# MCU.net
KiCad netlist of a schematic drawn in Altium Designer
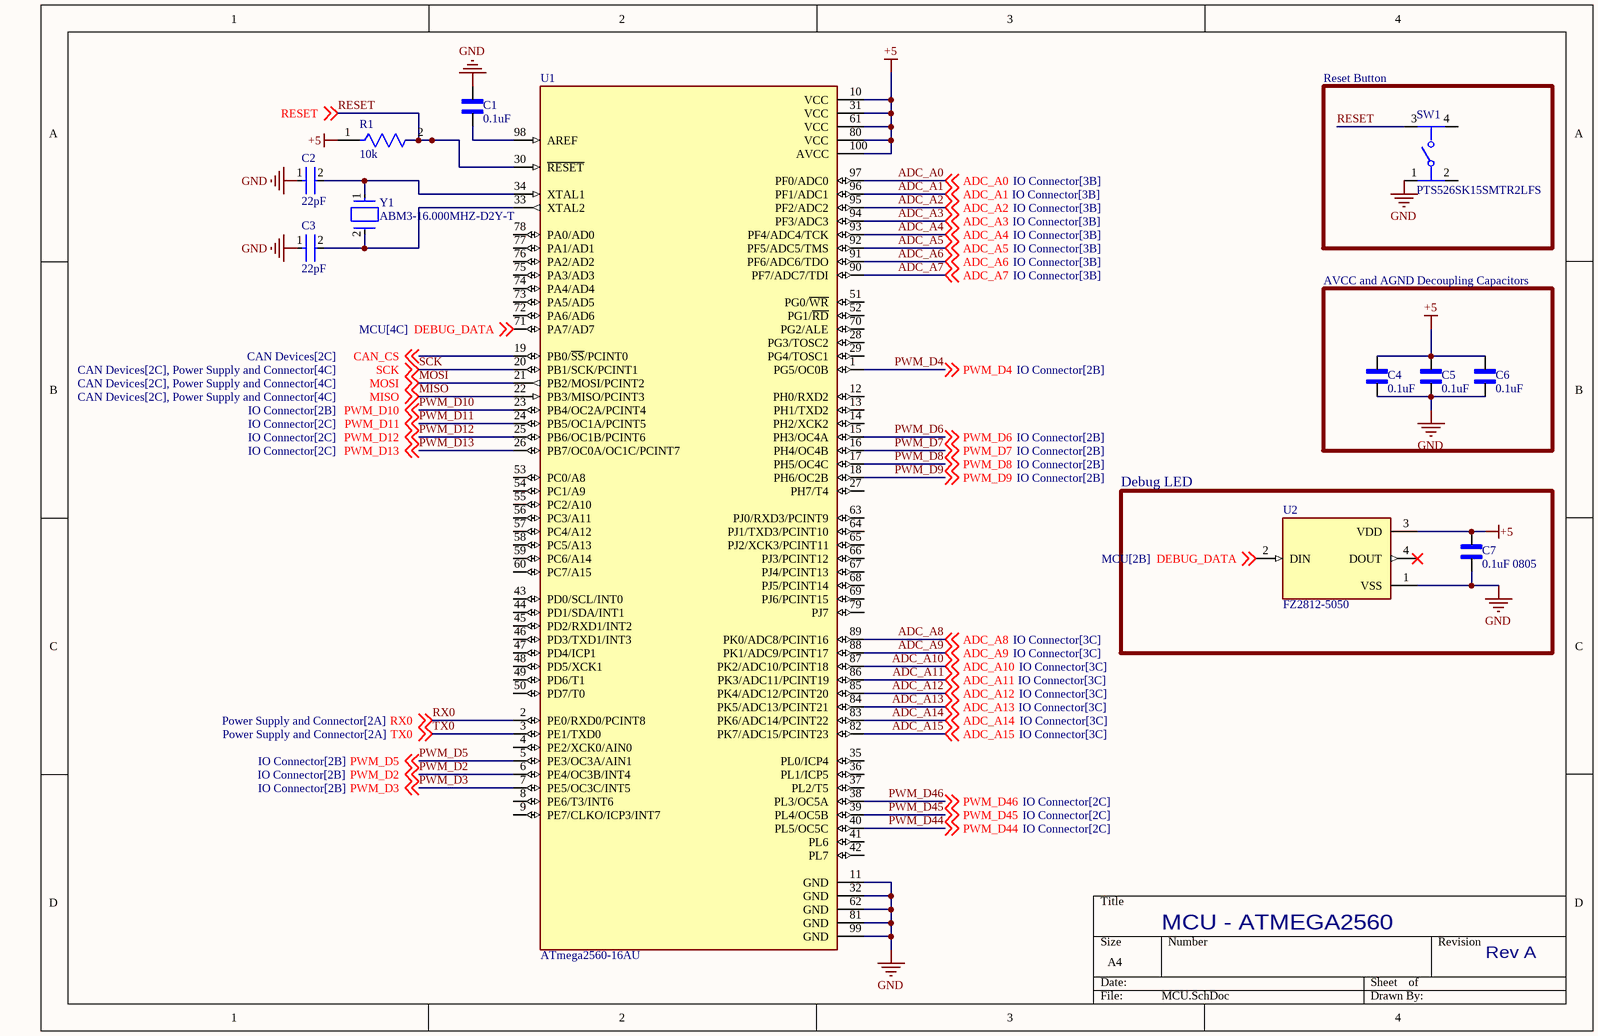
[diagram p0: MCU.SchDoc]

(export (version "E")
  (design (tool "Eeschema 10.0.6"))
  (components
    (comp (ref "C1")
      (value "0.1uF")
      (footprint "GCM21BR71H104KA37L:CAPC2012X135N")
      (description "CAP, MLCC, X7R, 0.1UF, 50V, 0805")
      (fields (field (name "MF") "{'manufacturer': u'Murata'}") (field (name "MP") "GCM21BR71H104KA37L"))
      (libsource (lib "*") (part "GCM21BR71H104KA37L"))
    )
    (comp (ref "C2")
      (value "22pF")
      (footprint "FP-C0805C-DN-MFG")
      (description "CAP CER 22PF 100V 5% NP0 0805")
      (fields
        (field (name "OCTOPART") "https://octopart.com/c0805c220j1gactu-kemet-3791395")
        (field (name "TOLERANCE") "0.05")
      )
      (libsource (lib "Altium Content Vault") (part "b4654b650e69147ec39a6b967a45e02"))
    )
    (comp (ref "C3")
      (value "22pF")
      (footprint "FP-C0805C-DN-MFG")
      (description "CAP CER 22PF 100V 5% NP0 0805")
      (fields
        (field (name "OCTOPART") "https://octopart.com/c0805c220j1gactu-kemet-3791395")
        (field (name "TOLERANCE") "0.05")
      )
      (libsource (lib "Altium Content Vault") (part "b4654b650e69147ec39a6b967a45e02"))
    )
    (comp (ref "C4")
      (value "0.1uF")
      (footprint "GCM21BR71H104KA37L:CAPC2012X135N")
      (description "CAP, MLCC, X7R, 0.1UF, 50V, 0805")
      (fields (field (name "MF") "{'manufacturer': u'Murata'}") (field (name "MP") "GCM21BR71H104KA37L"))
      (libsource (lib "*") (part "GCM21BR71H104KA37L"))
    )
    (comp (ref "C5")
      (value "0.1uF")
      (footprint "GCM21BR71H104KA37L:CAPC2012X135N")
      (description "CAP, MLCC, X7R, 0.1UF, 50V, 0805")
      (fields (field (name "MF") "{'manufacturer': u'Murata'}") (field (name "MP") "GCM21BR71H104KA37L"))
      (libsource (lib "*") (part "GCM21BR71H104KA37L"))
    )
    (comp (ref "C6")
      (value "0.1uF")
      (footprint "GCM21BR71H104KA37L:CAPC2012X135N")
      (description "CAP, MLCC, X7R, 0.1UF, 50V, 0805")
      (fields (field (name "MF") "{'manufacturer': u'Murata'}") (field (name "MP") "GCM21BR71H104KA37L"))
      (libsource (lib "*") (part "GCM21BR71H104KA37L"))
    )
    (comp (ref "C7")
      (value "0.1uF 0805")
      (footprint "GCM21BR71H104KA37L:CAPC2012X135N")
      (description "CAP, MLCC, X7R, 0.1UF, 50V, 0805")
      (fields (field (name "MF") "{'manufacturer': u'Murata'}") (field (name "MP") "GCM21BR71H104KA37L"))
      (libsource (lib "*") (part "GCM21BR71H104KA37L"))
    )
    (comp (ref "R1")
      (value "10k")
      (footprint "FP-CRCW0805-e3-IPC_A")
      (description "RES Thick Film, 10kΩ, 1%, 0.125W, 100ppm/°C, 0805")
      (fields (field (name "TOLERANCE") "1%"))
      (libsource (lib "Altium Content Vault") (part "1029c3af85768c4190bb7ad29bc67b5"))
    )
    (comp (ref "SW1")
      (value "PTS526SK15SMTR2LFS")
      (footprint "FP-PTS526SK15SMTR2LFS-MFG")
      (description "TACT 5.2 X 5.2, 1.5 MM H, 260GF,")
      (fields
        (field (name "MANUFACTURER") "C&K")
        (field (name "OCTOPART") "https://octopart.com/pts526+sk15+smtr2+lfs-c%26k+components-100617999")
      )
      (libsource (lib "Altium Content Vault") (part "b8895f3f4cefb76e1819d2863dba89b"))
    )
    (comp (ref "U1")
      (value "ATmega2560-16AU")
      (footprint "ATMEGA2560-16AU:QFP50P1600X1600X120-100N")
      (fields (field (name "MF") "{'manufacturer': u'Microchip Technology'}"))
      (libsource (lib "*") (part "ATmega2560-16AU"))
    )
    (comp (ref "U2")
      (value "FZ2812-5050")
      (footprint "FZ2812-5050:LED_FZ2812-5050")
      (fields (field (name "MF") "{'manufacturer': u'Feztek'}"))
      (libsource (lib "*") (part "FZ2812-5050"))
    )
    (comp (ref "Y1")
      (value "ABM3-16.000MHZ-D2Y-T")
      (footprint "FP-ABM3-MFG")
      (description "Crystal 16MHz ±20ppm 18pF SMD-2 5mm x 3.2mm")
      (fields (field (name "TOLERANCE") "20ppm"))
      (libsource (lib "Altium Content Vault") (part "c23a69dc6c9e2f18f2079038eb95dd1"))
    )
  )
  (nets
    (net (code "1") (name "+5") (class "Default")
      (node (ref "C4") (pin "1") (pinfunction "1_1") (pintype "passive"))
      (node (ref "C5") (pin "1") (pinfunction "1_1") (pintype "passive"))
      (node (ref "C6") (pin "1") (pinfunction "1_1") (pintype "passive"))
      (node (ref "C7") (pin "1") (pinfunction "1_1") (pintype "passive"))
      (node (ref "R1") (pin "1") (pinfunction "1_1") (pintype "passive"))
      (node (ref "U1") (pin "10") (pinfunction "VCC_10") (pintype "power_in"))
      (node (ref "U1") (pin "100") (pinfunction "AVCC_100") (pintype "power_in"))
      (node (ref "U1") (pin "31") (pinfunction "VCC_31") (pintype "power_in"))
      (node (ref "U1") (pin "61") (pinfunction "VCC_61") (pintype "power_in"))
      (node (ref "U1") (pin "80") (pinfunction "VCC_80") (pintype "power_in"))
      (node (ref "U2") (pin "3") (pinfunction "VDD_3") (pintype "power_in"))
    )
    (net (code "2") (name "ADC_A0") (class "Default")
      (node (ref "U1") (pin "97") (pinfunction "PF0/ADC0_97") (pintype "bidirectional"))
    )
    (net (code "3") (name "ADC_A1") (class "Default")
      (node (ref "U1") (pin "96") (pinfunction "PF1/ADC1_96") (pintype "bidirectional"))
    )
    (net (code "4") (name "ADC_A2") (class "Default")
      (node (ref "U1") (pin "95") (pinfunction "PF2/ADC2_95") (pintype "bidirectional"))
    )
    (net (code "5") (name "ADC_A3") (class "Default")
      (node (ref "U1") (pin "94") (pinfunction "PF3/ADC3_94") (pintype "bidirectional"))
    )
    (net (code "6") (name "ADC_A4") (class "Default")
      (node (ref "U1") (pin "93") (pinfunction "PF4/ADC4/TCK_93") (pintype "bidirectional"))
    )
    (net (code "7") (name "ADC_A5") (class "Default")
      (node (ref "U1") (pin "92") (pinfunction "PF5/ADC5/TMS_92") (pintype "bidirectional"))
    )
    (net (code "8") (name "ADC_A6") (class "Default")
      (node (ref "U1") (pin "91") (pinfunction "PF6/ADC6/TDO_91") (pintype "bidirectional"))
    )
    (net (code "9") (name "ADC_A7") (class "Default")
      (node (ref "U1") (pin "90") (pinfunction "PF7/ADC7/TDI_90") (pintype "bidirectional"))
    )
    (net (code "10") (name "ADC_A8") (class "Default")
      (node (ref "U1") (pin "89") (pinfunction "PK0/ADC8/PCINT16_89") (pintype "bidirectional"))
    )
    (net (code "11") (name "ADC_A9") (class "Default")
      (node (ref "U1") (pin "88") (pinfunction "PK1/ADC9/PCINT17_88") (pintype "bidirectional"))
    )
    (net (code "12") (name "ADC_A10") (class "Default")
      (node (ref "U1") (pin "87") (pinfunction "PK2/ADC10/PCINT18_87") (pintype "bidirectional"))
    )
    (net (code "13") (name "ADC_A11") (class "Default")
      (node (ref "U1") (pin "86") (pinfunction "PK3/ADC11/PCINT19_86") (pintype "bidirectional"))
    )
    (net (code "14") (name "ADC_A12") (class "Default")
      (node (ref "U1") (pin "85") (pinfunction "PK4/ADC12/PCINT20_85") (pintype "bidirectional"))
    )
    (net (code "15") (name "ADC_A13") (class "Default")
      (node (ref "U1") (pin "84") (pinfunction "PK5/ADC13/PCINT21_84") (pintype "bidirectional"))
    )
    (net (code "16") (name "ADC_A14") (class "Default")
      (node (ref "U1") (pin "83") (pinfunction "PK6/ADC14/PCINT22_83") (pintype "bidirectional"))
    )
    (net (code "17") (name "ADC_A15") (class "Default")
      (node (ref "U1") (pin "82") (pinfunction "PK7/ADC15/PCINT23_82") (pintype "bidirectional"))
    )
    (net (code "18") (name "CAN_CS") (class "Default")
      (node (ref "U1") (pin "19") (pinfunction "PB0/~{SS}/PCINT0_19") (pintype "bidirectional"))
    )
    (net (code "19") (name "DEBUG_DATA") (class "Default")
      (node (ref "U1") (pin "71") (pinfunction "PA7/AD7_71") (pintype "bidirectional"))
      (node (ref "U2") (pin "2") (pinfunction "DIN_2") (pintype "input"))
    )
    (net (code "20") (name "GND") (class "Default")
      (node (ref "C1") (pin "1") (pinfunction "1_1") (pintype "passive"))
      (node (ref "C2") (pin "1") (pinfunction "1_1") (pintype "passive"))
      (node (ref "C3") (pin "1") (pinfunction "1_1") (pintype "passive"))
      (node (ref "C4") (pin "2") (pinfunction "2_2") (pintype "power_in"))
      (node (ref "C5") (pin "2") (pinfunction "2_2") (pintype "power_in"))
      (node (ref "C6") (pin "2") (pinfunction "2_2") (pintype "power_in"))
      (node (ref "C7") (pin "2") (pinfunction "2_2") (pintype "power_in"))
      (node (ref "SW1") (pin "1") (pinfunction "1_1") (pintype "passive"))
      (node (ref "U1") (pin "11") (pinfunction "GND_11") (pintype "power_in"))
      (node (ref "U1") (pin "32") (pinfunction "GND_32") (pintype "power_in"))
      (node (ref "U1") (pin "62") (pinfunction "GND_62") (pintype "power_in"))
      (node (ref "U1") (pin "81") (pinfunction "GND_81") (pintype "power_in"))
      (node (ref "U1") (pin "99") (pinfunction "GND_99") (pintype "power_in"))
      (node (ref "U2") (pin "1") (pinfunction "VSS_1") (pintype "power_in"))
    )
    (net (code "21") (name "MISO") (class "Default")
      (node (ref "U1") (pin "22") (pinfunction "PB3/MISO/PCINT3_22") (pintype "input"))
    )
    (net (code "22") (name "MOSI") (class "Default")
      (node (ref "U1") (pin "21") (pinfunction "PB2/MOSI/PCINT2_21") (pintype "output"))
    )
    (net (code "23") (name "Net-(U1-AREF)") (class "Default")
      (node (ref "C1") (pin "2") (pinfunction "2_2") (pintype "power_in"))
      (node (ref "U1") (pin "98") (pinfunction "AREF_98") (pintype "input"))
    )
    (net (code "24") (name "Net-(U1-XTAL1)") (class "Default")
      (node (ref "C2") (pin "2") (pinfunction "2_2") (pintype "passive"))
      (node (ref "U1") (pin "34") (pinfunction "XTAL1_34") (pintype "input"))
      (node (ref "Y1") (pin "1") (pinfunction "1_1") (pintype "passive"))
    )
    (net (code "25") (name "Net-(U1-XTAL2)") (class "Default")
      (node (ref "C3") (pin "2") (pinfunction "2_2") (pintype "passive"))
      (node (ref "U1") (pin "33") (pinfunction "XTAL2_33") (pintype "output"))
      (node (ref "Y1") (pin "2") (pinfunction "2_2") (pintype "passive"))
    )
    (net (code "26") (name "PWM_D2") (class "Default")
      (node (ref "U1") (pin "6") (pinfunction "PE4/OC3B/INT4_6") (pintype "bidirectional"))
    )
    (net (code "27") (name "PWM_D3") (class "Default")
      (node (ref "U1") (pin "7") (pinfunction "PE5/OC3C/INT5_7") (pintype "bidirectional"))
    )
    (net (code "28") (name "PWM_D4") (class "Default")
      (node (ref "U1") (pin "1") (pinfunction "PG5/OC0B_1") (pintype "bidirectional"))
    )
    (net (code "29") (name "PWM_D5") (class "Default")
      (node (ref "U1") (pin "5") (pinfunction "PE3/OC3A/AIN1_5") (pintype "bidirectional"))
    )
    (net (code "30") (name "PWM_D6") (class "Default")
      (node (ref "U1") (pin "15") (pinfunction "PH3/OC4A_15") (pintype "bidirectional"))
    )
    (net (code "31") (name "PWM_D7") (class "Default")
      (node (ref "U1") (pin "16") (pinfunction "PH4/OC4B_16") (pintype "bidirectional"))
    )
    (net (code "32") (name "PWM_D8") (class "Default")
      (node (ref "U1") (pin "17") (pinfunction "PH5/OC4C_17") (pintype "bidirectional"))
    )
    (net (code "33") (name "PWM_D9") (class "Default")
      (node (ref "U1") (pin "18") (pinfunction "PH6/OC2B_18") (pintype "bidirectional"))
    )
    (net (code "34") (name "PWM_D10") (class "Default")
      (node (ref "U1") (pin "23") (pinfunction "PB4/OC2A/PCINT4_23") (pintype "bidirectional"))
    )
    (net (code "35") (name "PWM_D11") (class "Default")
      (node (ref "U1") (pin "24") (pinfunction "PB5/OC1A/PCINT5_24") (pintype "bidirectional"))
    )
    (net (code "36") (name "PWM_D12") (class "Default")
      (node (ref "U1") (pin "25") (pinfunction "PB6/OC1B/PCINT6_25") (pintype "bidirectional"))
    )
    (net (code "37") (name "PWM_D13") (class "Default")
      (node (ref "U1") (pin "26") (pinfunction "PB7/OC0A/OC1C/PCINT7_26") (pintype "bidirectional"))
    )
    (net (code "38") (name "PWM_D44") (class "Default")
      (node (ref "U1") (pin "40") (pinfunction "PL5/OC5C_40") (pintype "bidirectional"))
    )
    (net (code "39") (name "PWM_D45") (class "Default")
      (node (ref "U1") (pin "39") (pinfunction "PL4/OC5B_39") (pintype "bidirectional"))
    )
    (net (code "40") (name "PWM_D46") (class "Default")
      (node (ref "U1") (pin "38") (pinfunction "PL3/OC5A_38") (pintype "bidirectional"))
    )
    (net (code "41") (name "RESET") (class "Default")
      (node (ref "R1") (pin "2") (pinfunction "2_2") (pintype "power_in"))
      (node (ref "SW1") (pin "3") (pinfunction "3_3") (pintype "passive"))
      (node (ref "U1") (pin "30") (pinfunction "~{RESET}_30") (pintype "input"))
    )
    (net (code "42") (name "RX0") (class "Default")
      (node (ref "U1") (pin "2") (pinfunction "PE0/RXD0/PCINT8_2") (pintype "bidirectional"))
    )
    (net (code "43") (name "SCK") (class "Default")
      (node (ref "U1") (pin "20") (pinfunction "PB1/SCK/PCINT1_20") (pintype "bidirectional"))
    )
    (net (code "44") (name "TX0") (class "Default")
      (node (ref "U1") (pin "3") (pinfunction "PE1/TXD0_3") (pintype "bidirectional"))
    )
    (net (code "45") (name "unconnected-(SW1-Pad2)") (class "Default")
      (node (ref "SW1") (pin "2") (pinfunction "2_2") (pintype "passive"))
    )
    (net (code "46") (name "unconnected-(SW1-Pad4)") (class "Default")
      (node (ref "SW1") (pin "4") (pinfunction "4_4") (pintype "passive"))
    )
    (net (code "47") (name "unconnected-(U1-PA0{slash}AD0-Pad78)") (class "Default")
      (node (ref "U1") (pin "78") (pinfunction "PA0/AD0_78") (pintype "bidirectional"))
    )
    (net (code "48") (name "unconnected-(U1-PA1{slash}AD1-Pad77)") (class "Default")
      (node (ref "U1") (pin "77") (pinfunction "PA1/AD1_77") (pintype "bidirectional"))
    )
    (net (code "49") (name "unconnected-(U1-PA2{slash}AD2-Pad76)") (class "Default")
      (node (ref "U1") (pin "76") (pinfunction "PA2/AD2_76") (pintype "bidirectional"))
    )
    (net (code "50") (name "unconnected-(U1-PA3{slash}AD3-Pad75)") (class "Default")
      (node (ref "U1") (pin "75") (pinfunction "PA3/AD3_75") (pintype "bidirectional"))
    )
    (net (code "51") (name "unconnected-(U1-PA4{slash}AD4-Pad74)") (class "Default")
      (node (ref "U1") (pin "74") (pinfunction "PA4/AD4_74") (pintype "bidirectional"))
    )
    (net (code "52") (name "unconnected-(U1-PA5{slash}AD5-Pad73)") (class "Default")
      (node (ref "U1") (pin "73") (pinfunction "PA5/AD5_73") (pintype "bidirectional"))
    )
    (net (code "53") (name "unconnected-(U1-PA6{slash}AD6-Pad72)") (class "Default")
      (node (ref "U1") (pin "72") (pinfunction "PA6/AD6_72") (pintype "bidirectional"))
    )
    (net (code "54") (name "unconnected-(U1-PC0{slash}A8-Pad53)") (class "Default")
      (node (ref "U1") (pin "53") (pinfunction "PC0/A8_53") (pintype "bidirectional"))
    )
    (net (code "55") (name "unconnected-(U1-PC1{slash}A9-Pad54)") (class "Default")
      (node (ref "U1") (pin "54") (pinfunction "PC1/A9_54") (pintype "bidirectional"))
    )
    (net (code "56") (name "unconnected-(U1-PC2{slash}A10-Pad55)") (class "Default")
      (node (ref "U1") (pin "55") (pinfunction "PC2/A10_55") (pintype "bidirectional"))
    )
    (net (code "57") (name "unconnected-(U1-PC3{slash}A11-Pad56)") (class "Default")
      (node (ref "U1") (pin "56") (pinfunction "PC3/A11_56") (pintype "bidirectional"))
    )
    (net (code "58") (name "unconnected-(U1-PC4{slash}A12-Pad57)") (class "Default")
      (node (ref "U1") (pin "57") (pinfunction "PC4/A12_57") (pintype "bidirectional"))
    )
    (net (code "59") (name "unconnected-(U1-PC5{slash}A13-Pad58)") (class "Default")
      (node (ref "U1") (pin "58") (pinfunction "PC5/A13_58") (pintype "bidirectional"))
    )
    (net (code "60") (name "unconnected-(U1-PC6{slash}A14-Pad59)") (class "Default")
      (node (ref "U1") (pin "59") (pinfunction "PC6/A14_59") (pintype "bidirectional"))
    )
    (net (code "61") (name "unconnected-(U1-PC7{slash}A15-Pad60)") (class "Default")
      (node (ref "U1") (pin "60") (pinfunction "PC7/A15_60") (pintype "bidirectional"))
    )
    (net (code "62") (name "unconnected-(U1-PD0{slash}SCL{slash}INT0-Pad43)") (class "Default")
      (node (ref "U1") (pin "43") (pinfunction "PD0/SCL/INT0_43") (pintype "bidirectional"))
    )
    (net (code "63") (name "unconnected-(U1-PD1{slash}SDA{slash}INT1-Pad44)") (class "Default")
      (node (ref "U1") (pin "44") (pinfunction "PD1/SDA/INT1_44") (pintype "bidirectional"))
    )
    (net (code "64") (name "unconnected-(U1-PD2{slash}RXD1{slash}INT2-Pad45)") (class "Default")
      (node (ref "U1") (pin "45") (pinfunction "PD2/RXD1/INT2_45") (pintype "bidirectional"))
    )
    (net (code "65") (name "unconnected-(U1-PD3{slash}TXD1{slash}INT3-Pad46)") (class "Default")
      (node (ref "U1") (pin "46") (pinfunction "PD3/TXD1/INT3_46") (pintype "bidirectional"))
    )
    (net (code "66") (name "unconnected-(U1-PD4{slash}ICP1-Pad47)") (class "Default")
      (node (ref "U1") (pin "47") (pinfunction "PD4/ICP1_47") (pintype "bidirectional"))
    )
    (net (code "67") (name "unconnected-(U1-PD5{slash}XCK1-Pad48)") (class "Default")
      (node (ref "U1") (pin "48") (pinfunction "PD5/XCK1_48") (pintype "bidirectional"))
    )
    (net (code "68") (name "unconnected-(U1-PD6{slash}T1-Pad49)") (class "Default")
      (node (ref "U1") (pin "49") (pinfunction "PD6/T1_49") (pintype "bidirectional"))
    )
    (net (code "69") (name "unconnected-(U1-PD7{slash}T0-Pad50)") (class "Default")
      (node (ref "U1") (pin "50") (pinfunction "PD7/T0_50") (pintype "bidirectional"))
    )
    (net (code "70") (name "unconnected-(U1-PE2{slash}XCK0{slash}AIN0-Pad4)") (class "Default")
      (node (ref "U1") (pin "4") (pinfunction "PE2/XCK0/AIN0_4") (pintype "bidirectional"))
    )
    (net (code "71") (name "unconnected-(U1-PE6{slash}T3{slash}INT6-Pad8)") (class "Default")
      (node (ref "U1") (pin "8") (pinfunction "PE6/T3/INT6_8") (pintype "bidirectional"))
    )
    (net (code "72") (name "unconnected-(U1-PE7{slash}CLKO{slash}ICP3{slash}INT7-Pad9)") (class "Default")
      (node (ref "U1") (pin "9") (pinfunction "PE7/CLKO/ICP3/INT7_9") (pintype "bidirectional"))
    )
    (net (code "73") (name "unconnected-(U1-PG0{slash}~{WR}-Pad51)") (class "Default")
      (node (ref "U1") (pin "51") (pinfunction "PG0/~{WR}_51") (pintype "bidirectional"))
    )
    (net (code "74") (name "unconnected-(U1-PG1{slash}~{RD}-Pad52)") (class "Default")
      (node (ref "U1") (pin "52") (pinfunction "PG1/~{RD}_52") (pintype "bidirectional"))
    )
    (net (code "75") (name "unconnected-(U1-PG2{slash}ALE-Pad70)") (class "Default")
      (node (ref "U1") (pin "70") (pinfunction "PG2/ALE_70") (pintype "bidirectional"))
    )
    (net (code "76") (name "unconnected-(U1-PG3{slash}TOSC2-Pad28)") (class "Default")
      (node (ref "U1") (pin "28") (pinfunction "PG3/TOSC2_28") (pintype "bidirectional"))
    )
    (net (code "77") (name "unconnected-(U1-PG4{slash}TOSC1-Pad29)") (class "Default")
      (node (ref "U1") (pin "29") (pinfunction "PG4/TOSC1_29") (pintype "bidirectional"))
    )
    (net (code "78") (name "unconnected-(U1-PH0{slash}RXD2-Pad12)") (class "Default")
      (node (ref "U1") (pin "12") (pinfunction "PH0/RXD2_12") (pintype "bidirectional"))
    )
    (net (code "79") (name "unconnected-(U1-PH1{slash}TXD2-Pad13)") (class "Default")
      (node (ref "U1") (pin "13") (pinfunction "PH1/TXD2_13") (pintype "bidirectional"))
    )
    (net (code "80") (name "unconnected-(U1-PH2{slash}XCK2-Pad14)") (class "Default")
      (node (ref "U1") (pin "14") (pinfunction "PH2/XCK2_14") (pintype "bidirectional"))
    )
    (net (code "81") (name "unconnected-(U1-PH7{slash}T4-Pad27)") (class "Default")
      (node (ref "U1") (pin "27") (pinfunction "PH7/T4_27") (pintype "bidirectional"))
    )
    (net (code "82") (name "unconnected-(U1-PJ0{slash}RXD3{slash}PCINT9-Pad63)") (class "Default")
      (node (ref "U1") (pin "63") (pinfunction "PJ0/RXD3/PCINT9_63") (pintype "bidirectional"))
    )
    (net (code "83") (name "unconnected-(U1-PJ1{slash}TXD3{slash}PCINT10-Pad64)") (class "Default")
      (node (ref "U1") (pin "64") (pinfunction "PJ1/TXD3/PCINT10_64") (pintype "bidirectional"))
    )
    (net (code "84") (name "unconnected-(U1-PJ2{slash}XCK3{slash}PCINT11-Pad65)") (class "Default")
      (node (ref "U1") (pin "65") (pinfunction "PJ2/XCK3/PCINT11_65") (pintype "bidirectional"))
    )
    (net (code "85") (name "unconnected-(U1-PJ3{slash}PCINT12-Pad66)") (class "Default")
      (node (ref "U1") (pin "66") (pinfunction "PJ3/PCINT12_66") (pintype "bidirectional"))
    )
    (net (code "86") (name "unconnected-(U1-PJ4{slash}PCINT13-Pad67)") (class "Default")
      (node (ref "U1") (pin "67") (pinfunction "PJ4/PCINT13_67") (pintype "bidirectional"))
    )
    (net (code "87") (name "unconnected-(U1-PJ5{slash}PCINT14-Pad68)") (class "Default")
      (node (ref "U1") (pin "68") (pinfunction "PJ5/PCINT14_68") (pintype "bidirectional"))
    )
    (net (code "88") (name "unconnected-(U1-PJ6{slash}PCINT15-Pad69)") (class "Default")
      (node (ref "U1") (pin "69") (pinfunction "PJ6/PCINT15_69") (pintype "bidirectional"))
    )
    (net (code "89") (name "unconnected-(U1-PJ7-Pad79)") (class "Default")
      (node (ref "U1") (pin "79") (pinfunction "PJ7_79") (pintype "bidirectional"))
    )
    (net (code "90") (name "unconnected-(U1-PL0{slash}ICP4-Pad35)") (class "Default")
      (node (ref "U1") (pin "35") (pinfunction "PL0/ICP4_35") (pintype "bidirectional"))
    )
    (net (code "91") (name "unconnected-(U1-PL1{slash}ICP5-Pad36)") (class "Default")
      (node (ref "U1") (pin "36") (pinfunction "PL1/ICP5_36") (pintype "bidirectional"))
    )
    (net (code "92") (name "unconnected-(U1-PL2{slash}T5-Pad37)") (class "Default")
      (node (ref "U1") (pin "37") (pinfunction "PL2/T5_37") (pintype "bidirectional"))
    )
    (net (code "93") (name "unconnected-(U1-PL6-Pad41)") (class "Default")
      (node (ref "U1") (pin "41") (pinfunction "PL6_41") (pintype "bidirectional"))
    )
    (net (code "94") (name "unconnected-(U1-PL7-Pad42)") (class "Default")
      (node (ref "U1") (pin "42") (pinfunction "PL7_42") (pintype "bidirectional"))
    )
    (net (code "95") (name "unconnected-(U2-DOUT-Pad4)") (class "Default")
      (node (ref "U2") (pin "4") (pinfunction "DOUT_4") (pintype "output+no_connect"))
    )
  )
)
